# x-Link.net
KiCad netlist of a schematic drawn in Altium Designer
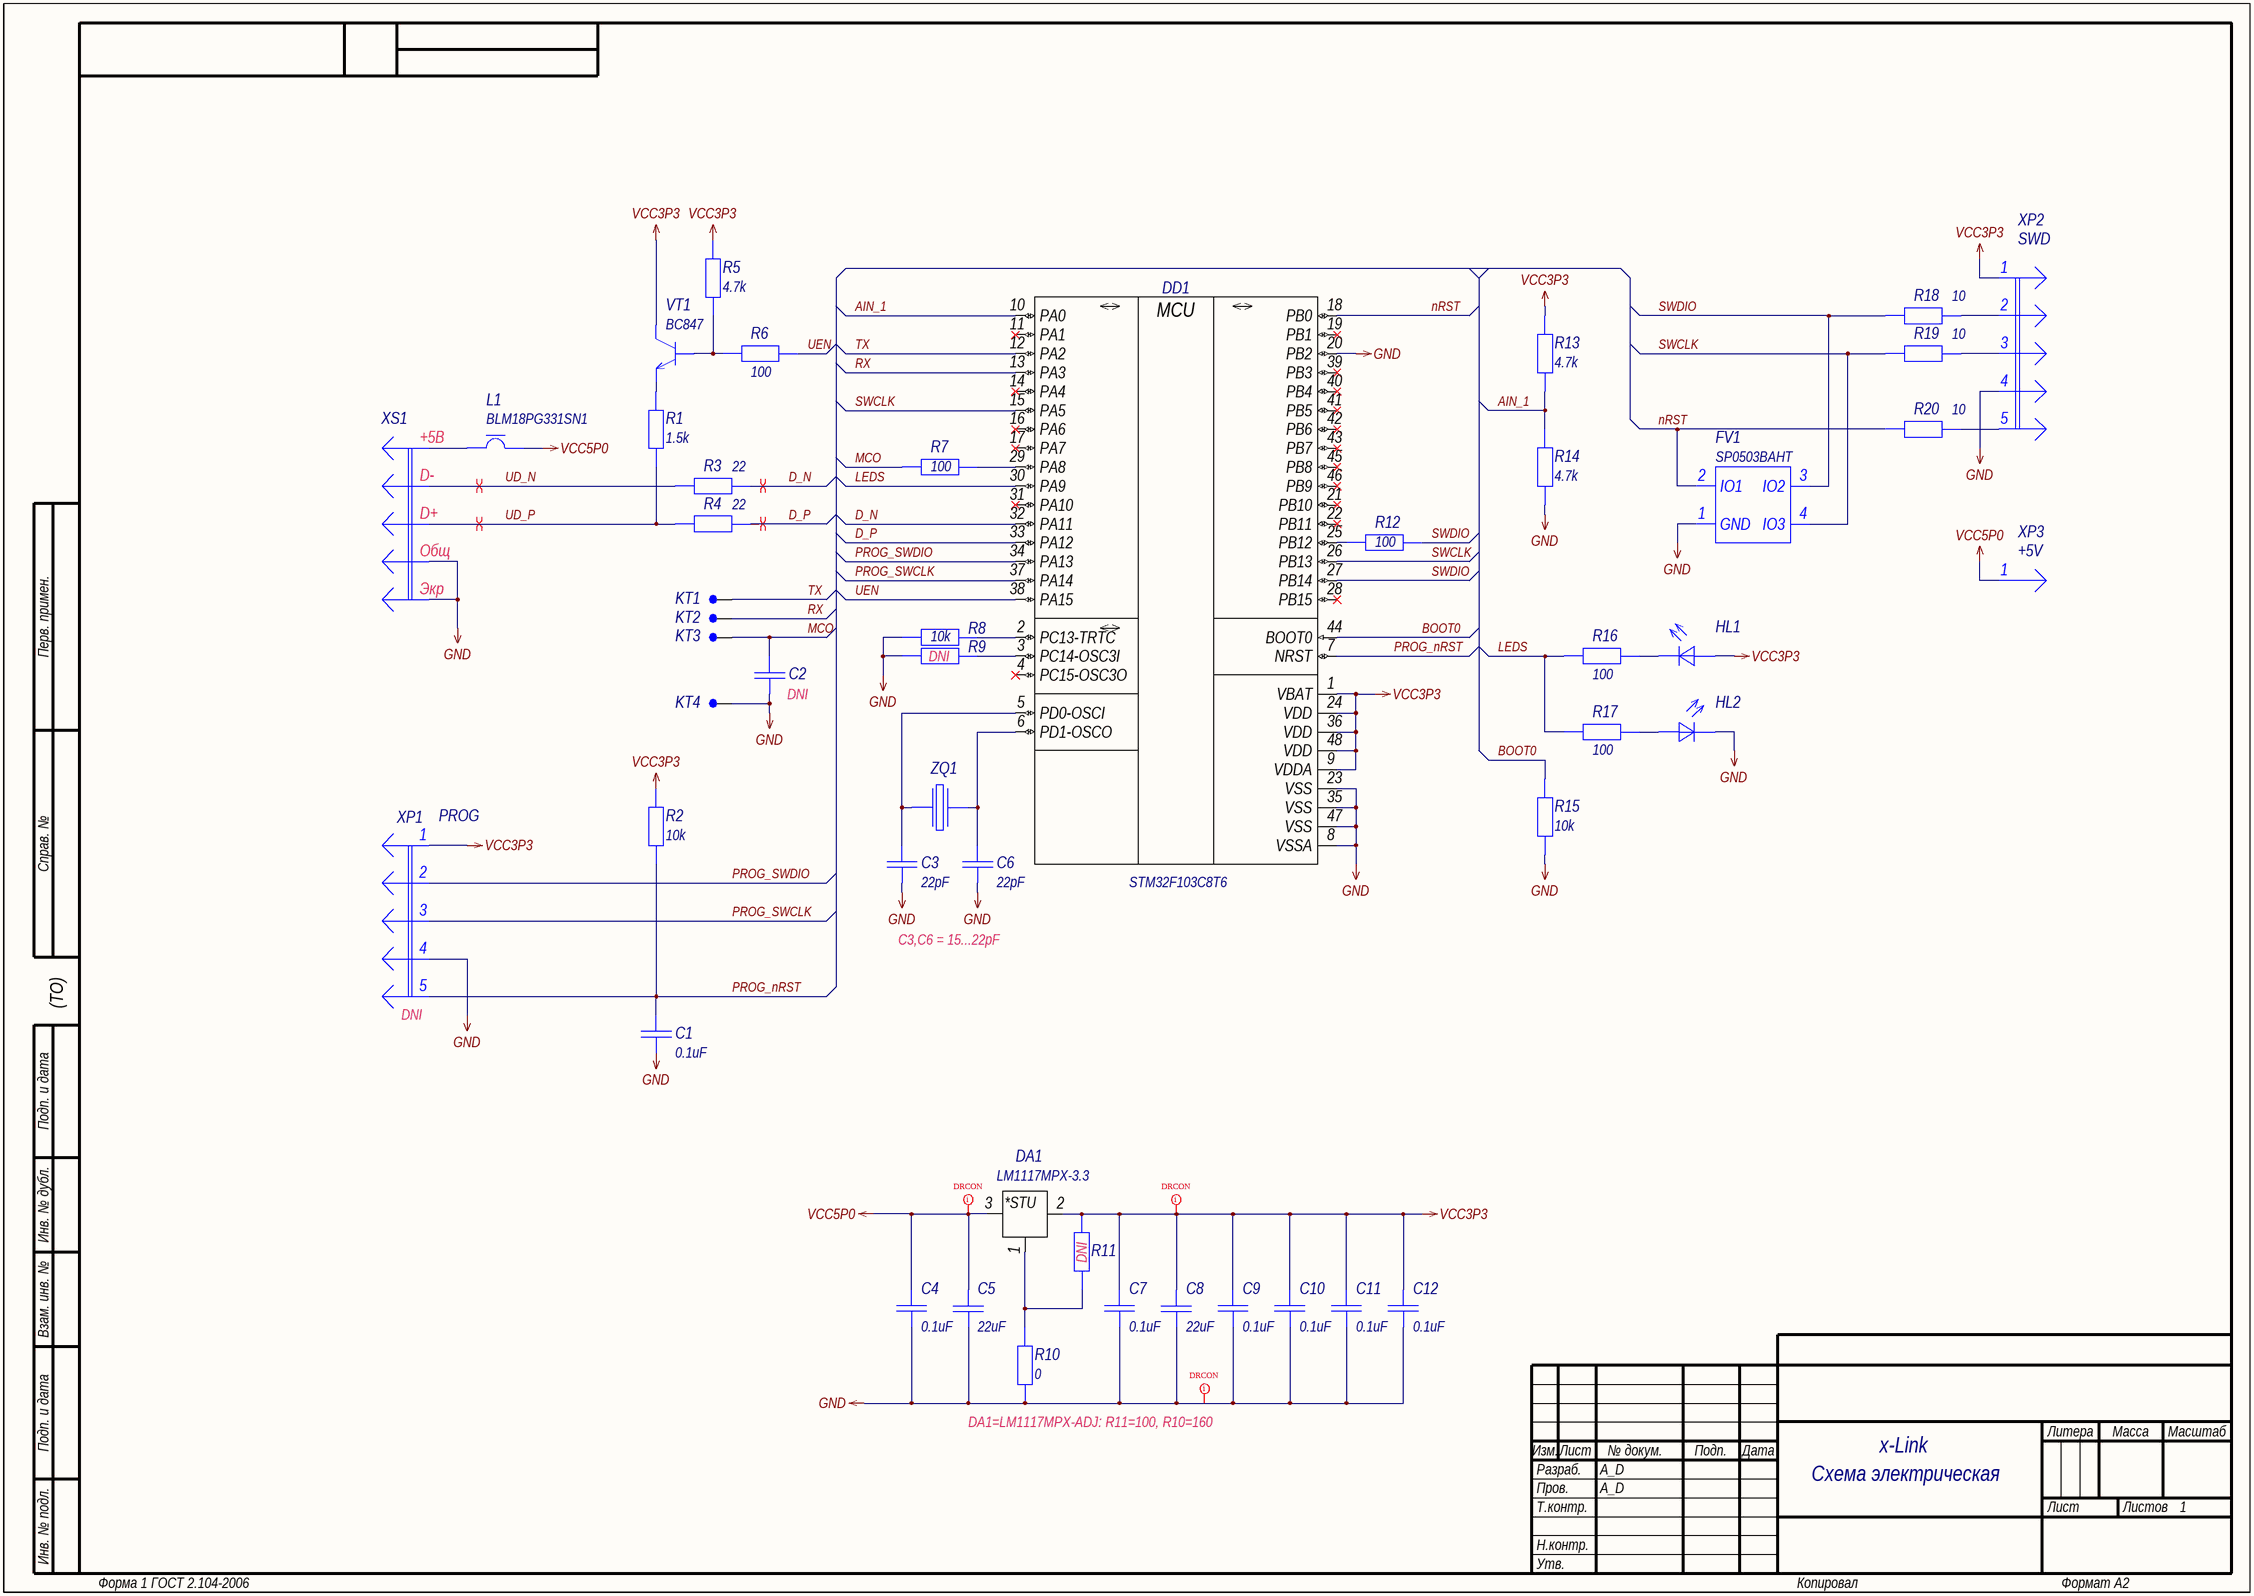
[diagram p0: x-Link.SchDoc]

(export (version "E")
  (design (tool "Eeschema 10.0.6"))
  (components
    (comp (ref "C1")
      (value "0.1uF")
      (footprint "C0603_L")
      (fields
        (field (name "PART NUMBER") "GRM188R71C104KA01D")
        (field (name "VOLTAGE") "16V")
        (field (name "TOLERANCE") "±10%")
        (field (name "PUBLISHER") "Andrew Danich")
      )
      (libsource (lib "Lib_IMP_GOST") (part "Capacitor"))
    )
    (comp (ref "C2")
      (value "Capacitor")
      (footprint "C0603_L")
      (fields
        (field (name "PART NUMBER") "GRM1885C1H220JA01D")
        (field (name "VOLTAGE") "50V")
        (field (name "TOLERANCE") "±5%")
        (field (name "PUBLISHER") "Andrew Danich")
      )
      (libsource (lib "Lib_IMP_GOST") (part "Capacitor"))
    )
    (comp (ref "C3")
      (value "22pF")
      (footprint "C0603_L")
      (fields
        (field (name "PART NUMBER") "GRM1885C1H220JA01D")
        (field (name "VOLTAGE") "50V")
        (field (name "TOLERANCE") "±5%")
        (field (name "PUBLISHER") "Andrew Danich")
      )
      (libsource (lib "Lib_IMP_GOST") (part "Capacitor"))
    )
    (comp (ref "C4")
      (value "0.1uF")
      (footprint "C0603_L")
      (fields
        (field (name "PART NUMBER") "GRM188R71C104KA01D")
        (field (name "VOLTAGE") "16V")
        (field (name "TOLERANCE") "±10%")
        (field (name "PUBLISHER") "Andrew Danich")
      )
      (libsource (lib "Lib_IMP_GOST") (part "Capacitor"))
    )
    (comp (ref "C5")
      (value "22uF")
      (footprint "C0805_L")
      (fields
        (field (name "PART NUMBER") "GRM21BR60J226ME39L")
        (field (name "VOLTAGE") "6.3V")
        (field (name "TOLERANCE") "±20%")
        (field (name "PUBLISHER") "Andrew Danich")
      )
      (libsource (lib "Lib_IMP_GOST") (part "Capacitor"))
    )
    (comp (ref "C6")
      (value "22pF")
      (footprint "C0603_L")
      (fields
        (field (name "PART NUMBER") "GRM1885C1H220JA01D")
        (field (name "VOLTAGE") "50V")
        (field (name "TOLERANCE") "±5%")
        (field (name "PUBLISHER") "Andrew Danich")
      )
      (libsource (lib "Lib_IMP_GOST") (part "Capacitor"))
    )
    (comp (ref "C7")
      (value "0.1uF")
      (footprint "C0603_L")
      (fields
        (field (name "PART NUMBER") "GRM188R71C104KA01D")
        (field (name "VOLTAGE") "16V")
        (field (name "TOLERANCE") "±10%")
        (field (name "PUBLISHER") "Andrew Danich")
      )
      (libsource (lib "Lib_IMP_GOST") (part "Capacitor"))
    )
    (comp (ref "C8")
      (value "22uF")
      (footprint "C0805_L")
      (fields
        (field (name "PART NUMBER") "GRM21BR60J226ME39L")
        (field (name "VOLTAGE") "6.3V")
        (field (name "TOLERANCE") "±20%")
        (field (name "PUBLISHER") "Andrew Danich")
      )
      (libsource (lib "Lib_IMP_GOST") (part "Capacitor"))
    )
    (comp (ref "C9")
      (value "0.1uF")
      (footprint "C0603_L")
      (fields
        (field (name "PART NUMBER") "GRM188R71C104KA01D")
        (field (name "VOLTAGE") "16V")
        (field (name "TOLERANCE") "±10%")
        (field (name "PUBLISHER") "Andrew Danich")
      )
      (libsource (lib "Lib_IMP_GOST") (part "Capacitor"))
    )
    (comp (ref "C10")
      (value "0.1uF")
      (footprint "C0603_L")
      (fields
        (field (name "PART NUMBER") "GRM188R71C104KA01D")
        (field (name "VOLTAGE") "16V")
        (field (name "TOLERANCE") "±10%")
        (field (name "PUBLISHER") "Andrew Danich")
      )
      (libsource (lib "Lib_IMP_GOST") (part "Capacitor"))
    )
    (comp (ref "C11")
      (value "0.1uF")
      (footprint "C0603_L")
      (fields
        (field (name "PART NUMBER") "GRM188R71C104KA01D")
        (field (name "VOLTAGE") "16V")
        (field (name "TOLERANCE") "±10%")
        (field (name "PUBLISHER") "Andrew Danich")
      )
      (libsource (lib "Lib_IMP_GOST") (part "Capacitor"))
    )
    (comp (ref "C12")
      (value "0.1uF")
      (footprint "C0603_L")
      (fields
        (field (name "PART NUMBER") "GRM188R71C104KA01D")
        (field (name "VOLTAGE") "16V")
        (field (name "TOLERANCE") "±10%")
        (field (name "PUBLISHER") "Andrew Danich")
      )
      (libsource (lib "Lib_IMP_GOST") (part "Capacitor"))
    )
    (comp (ref "DA1")
      (value "LM1117MPX-3.3")
      (footprint "SOT-223")
      (fields (field (name "Comment") "LM1117-Series") (field (name "PUBLISHER") "Andrew Danich"))
      (libsource (lib "Lib_IMP_GOST") (part "LM1117-Series"))
    )
    (comp (ref "DD1")
      (value "STM32F103C8T6")
      (footprint "LQFP-48")
      (fields
        (field (name "MANUFACTURER") "STMicroelectronics")
        (field (name "Comment") "STM32F103Cxxx-Series")
        (field (name "PUBLISHER") "Andrew Danich")
      )
      (libsource (lib "Lib_IMP_GOST") (part "STM32F103Cxxx-Series"))
    )
    (comp (ref "FV1")
      (value "SP0503BAHT")
      (footprint "SOT-143")
      (fields (field (name "MANUFACTURER") "LittleFuse") (field (name "PUBLISHER") "Andrew Danich"))
      (libsource (lib "Lib_IMP_GOST") (part "SP0503BAHT"))
    )
    (comp (ref "HL1")
      (value "Text")
      (footprint "LD0603_L")
      (fields (field (name "PART NUMBER") "BL-LS0603GC") (field (name "PUBLISHER") "Andrew Danich"))
      (libsource (lib "Lib_IMP_GOST") (part "Led-1"))
    )
    (comp (ref "HL2")
      (value "Text")
      (footprint "LD0603_L")
      (fields (field (name "PART NUMBER") "BL-LS0603HC") (field (name "PUBLISHER") "Andrew Danich"))
      (libsource (lib "Lib_IMP_GOST") (part "Led-1"))
    )
    (comp (ref "KT1")
      (value "TX")
      (footprint "TP-SMT-C-1mm-1")
      (fields (field (name "PART NUMBER") "КТ-SMT-1") (field (name "PUBLISHER") "Andrew Danich"))
      (libsource (lib "Lib_IMP_GOST") (part "TP-S-1"))
    )
    (comp (ref "KT2")
      (value "RX")
      (footprint "TP-SMT-C-1mm-1")
      (fields (field (name "PART NUMBER") "КТ-SMT-1") (field (name "PUBLISHER") "Andrew Danich"))
      (libsource (lib "Lib_IMP_GOST") (part "TP-S-1"))
    )
    (comp (ref "KT3")
      (value "MCO")
      (footprint "TP-SMT-C-1mm-1")
      (fields (field (name "PART NUMBER") "КТ-SMT-1") (field (name "PUBLISHER") "Andrew Danich"))
      (libsource (lib "Lib_IMP_GOST") (part "TP-S-1"))
    )
    (comp (ref "KT4")
      (value "GND")
      (footprint "TP-SMT-C-1mm-1")
      (fields (field (name "PART NUMBER") "КТ-SMT-1") (field (name "PUBLISHER") "Andrew Danich"))
      (libsource (lib "Lib_IMP_GOST") (part "TP-S-1"))
    )
    (comp (ref "L1")
      (value "BLM18PG331SN1")
      (footprint "L0603_L")
      (fields
        (field (name "MANUFACTURER") "Murata")
        (field (name "Comment") "FerriteBead")
        (field (name "PUBLISHER") "Andrew Danich")
      )
      (libsource (lib "Lib_IMP_GOST") (part "FerriteBead"))
    )
    (comp (ref "R1")
      (value "1.5k")
      (footprint "R0603_L")
      (fields
        (field (name "PART NUMBER") "RC0603JR-071K5L")
        (field (name "TOLERANCE") "±5%")
        (field (name "MANUFACTURER") "Yageo")
        (field (name "PUBLISHER") "Andrew Danich")
      )
      (libsource (lib "Lib_IMP_GOST") (part "Resistor"))
    )
    (comp (ref "R2")
      (value "10k")
      (footprint "R0603_L")
      (fields
        (field (name "PART NUMBER") "RC0603JR-0710KL")
        (field (name "TOLERANCE") "±5%")
        (field (name "MANUFACTURER") "Yageo")
        (field (name "PUBLISHER") "Andrew Danich")
      )
      (libsource (lib "Lib_IMP_GOST") (part "Resistor"))
    )
    (comp (ref "R3")
      (value "22")
      (footprint "R0603_L")
      (fields
        (field (name "PART NUMBER") "RC0603JR-0722RL")
        (field (name "TOLERANCE") "±5%")
        (field (name "MANUFACTURER") "Yageo")
        (field (name "PUBLISHER") "Andrew Danich")
      )
      (libsource (lib "Lib_IMP_GOST") (part "Resistor"))
    )
    (comp (ref "R4")
      (value "22")
      (footprint "R0603_L")
      (fields
        (field (name "PART NUMBER") "RC0603JR-0722RL")
        (field (name "TOLERANCE") "±5%")
        (field (name "MANUFACTURER") "Yageo")
        (field (name "PUBLISHER") "Andrew Danich")
      )
      (libsource (lib "Lib_IMP_GOST") (part "Resistor"))
    )
    (comp (ref "R5")
      (value "4.7k")
      (footprint "R0603_L")
      (fields
        (field (name "PART NUMBER") "RC0603JR-074K7L")
        (field (name "TOLERANCE") "±5%")
        (field (name "MANUFACTURER") "Yageo")
        (field (name "PUBLISHER") "Andrew Danich")
      )
      (libsource (lib "Lib_IMP_GOST") (part "Resistor"))
    )
    (comp (ref "R6")
      (value "100")
      (footprint "R0603_L")
      (fields
        (field (name "PART NUMBER") "RC0603JR-07100R")
        (field (name "TOLERANCE") "±5%")
        (field (name "MANUFACTURER") "Yageo")
        (field (name "PUBLISHER") "Andrew Danich")
      )
      (libsource (lib "Lib_IMP_GOST") (part "Resistor"))
    )
    (comp (ref "R7")
      (value "100")
      (footprint "R0603_L")
      (fields
        (field (name "PART NUMBER") "RC0603JR-07100R")
        (field (name "TOLERANCE") "±5%")
        (field (name "MANUFACTURER") "Yageo")
        (field (name "PUBLISHER") "Andrew Danich")
      )
      (libsource (lib "Lib_IMP_GOST") (part "Resistor"))
    )
    (comp (ref "R8")
      (value "10k")
      (footprint "R0603_L")
      (fields
        (field (name "PART NUMBER") "RC0603JR-0710KL")
        (field (name "TOLERANCE") "±5%")
        (field (name "MANUFACTURER") "Yageo")
        (field (name "PUBLISHER") "Andrew Danich")
      )
      (libsource (lib "Lib_IMP_GOST") (part "Resistor"))
    )
    (comp (ref "R9")
      (value "Resistor")
      (footprint "R0603_L")
      (fields
        (field (name "PART NUMBER") "RC0603JR-0710KL")
        (field (name "TOLERANCE") "±5%")
        (field (name "MANUFACTURER") "Yageo")
        (field (name "PUBLISHER") "Andrew Danich")
      )
      (libsource (lib "Lib_IMP_GOST") (part "Resistor"))
    )
    (comp (ref "R10")
      (value "0")
      (footprint "R0603_L")
      (fields
        (field (name "PART NUMBER") "RC0603JR-070R")
        (field (name "TOLERANCE") "±5%")
        (field (name "MANUFACTURER") "Yageo")
        (field (name "PUBLISHER") "Andrew Danich")
      )
      (libsource (lib "Lib_IMP_GOST") (part "Resistor"))
    )
    (comp (ref "R11")
      (value "Resistor")
      (footprint "R0603_L")
      (fields
        (field (name "PART NUMBER") "RC0603JR-070R")
        (field (name "TOLERANCE") "±5%")
        (field (name "MANUFACTURER") "Yageo")
        (field (name "PUBLISHER") "Andrew Danich")
      )
      (libsource (lib "Lib_IMP_GOST") (part "Resistor"))
    )
    (comp (ref "R12")
      (value "100")
      (footprint "R0603_L")
      (fields
        (field (name "PART NUMBER") "RC0603JR-07100R")
        (field (name "TOLERANCE") "±5%")
        (field (name "MANUFACTURER") "Yageo")
        (field (name "PUBLISHER") "Andrew Danich")
      )
      (libsource (lib "Lib_IMP_GOST") (part "Resistor"))
    )
    (comp (ref "R13")
      (value "4.7k")
      (footprint "R0603_L")
      (fields
        (field (name "PART NUMBER") "RC0603JR-074K7L")
        (field (name "TOLERANCE") "±5%")
        (field (name "MANUFACTURER") "Yageo")
        (field (name "PUBLISHER") "Andrew Danich")
      )
      (libsource (lib "Lib_IMP_GOST") (part "Resistor"))
    )
    (comp (ref "R14")
      (value "4.7k")
      (footprint "R0603_L")
      (fields
        (field (name "PART NUMBER") "RC0603JR-074K7L")
        (field (name "TOLERANCE") "±5%")
        (field (name "MANUFACTURER") "Yageo")
        (field (name "PUBLISHER") "Andrew Danich")
      )
      (libsource (lib "Lib_IMP_GOST") (part "Resistor"))
    )
    (comp (ref "R15")
      (value "10k")
      (footprint "R0603_L")
      (fields
        (field (name "PART NUMBER") "RC0603JR-0710KL")
        (field (name "TOLERANCE") "±5%")
        (field (name "MANUFACTURER") "Yageo")
        (field (name "PUBLISHER") "Andrew Danich")
      )
      (libsource (lib "Lib_IMP_GOST") (part "Resistor"))
    )
    (comp (ref "R16")
      (value "100")
      (footprint "R0603_L")
      (fields
        (field (name "PART NUMBER") "RC0603JR-07100R")
        (field (name "TOLERANCE") "±5%")
        (field (name "MANUFACTURER") "Yageo")
        (field (name "PUBLISHER") "Andrew Danich")
      )
      (libsource (lib "Lib_IMP_GOST") (part "Resistor"))
    )
    (comp (ref "R17")
      (value "100")
      (footprint "R0603_L")
      (fields
        (field (name "PART NUMBER") "RC0603JR-07100R")
        (field (name "TOLERANCE") "±5%")
        (field (name "MANUFACTURER") "Yageo")
        (field (name "PUBLISHER") "Andrew Danich")
      )
      (libsource (lib "Lib_IMP_GOST") (part "Resistor"))
    )
    (comp (ref "R18")
      (value "10")
      (footprint "R0603_L")
      (fields
        (field (name "PART NUMBER") "RC0603JR-0710RL")
        (field (name "TOLERANCE") "±5%")
        (field (name "MANUFACTURER") "Yageo")
        (field (name "PUBLISHER") "Andrew Danich")
      )
      (libsource (lib "Lib_IMP_GOST") (part "Resistor"))
    )
    (comp (ref "R19")
      (value "10")
      (footprint "R0603_L")
      (fields
        (field (name "PART NUMBER") "RC0603JR-0710RL")
        (field (name "TOLERANCE") "±5%")
        (field (name "MANUFACTURER") "Yageo")
        (field (name "PUBLISHER") "Andrew Danich")
      )
      (libsource (lib "Lib_IMP_GOST") (part "Resistor"))
    )
    (comp (ref "R20")
      (value "10")
      (footprint "R0603_L")
      (fields
        (field (name "PART NUMBER") "RC0603JR-0710RL")
        (field (name "TOLERANCE") "±5%")
        (field (name "MANUFACTURER") "Yageo")
        (field (name "PUBLISHER") "Andrew Danich")
      )
      (libsource (lib "Lib_IMP_GOST") (part "Resistor"))
    )
    (comp (ref "VT1")
      (value "BC847")
      (footprint "SOT-23")
      (fields (field (name "Comment") "BJT-NPN") (field (name "PUBLISHER") "Andrew Danich"))
      (libsource (lib "Lib_IMP_GOST") (part "BJT-NPN"))
    )
    (comp (ref "XP1")
      (value "PROG")
      (footprint "PLS-5")
      (fields (field (name "PART NUMBER") "PLS-5") (field (name "PUBLISHER") "Andrew Danich"))
      (libsource (lib "Lib_IMP_GOST") (part "Con-5-M"))
    )
    (comp (ref "XP2")
      (value "SWD")
      (footprint "PLS-5")
      (fields (field (name "PART NUMBER") "PLS-5") (field (name "PUBLISHER") "Andrew Danich"))
      (libsource (lib "Lib_IMP_GOST") (part "Con-5-M"))
    )
    (comp (ref "XP3")
      (value "+5V")
      (footprint "PLS-1")
      (fields (field (name "PART NUMBER") "PLS-1") (field (name "PUBLISHER") "Andrew Danich"))
      (libsource (lib "Lib_IMP_GOST") (part "Con-1-M"))
    )
    (comp (ref "XS1")
      (value "Text")
      (footprint "DS1097")
      (fields
        (field (name "PART NUMBER") "DS1097-B")
        (field (name "MANUFACTURER") "Connfly Electronic Co., Ltd")
        (field (name "PUBLISHER") "Andrew Danich")
      )
      (libsource (lib "Lib_IMP_GOST") (part "Con-5-M-USB"))
    )
    (comp (ref "ZQ1")
      (value "Crystal")
      (footprint "SMD 5x3.2mm")
      (fields
        (field (name "PART NUMBER") "KX-9A 8.0 MHz 30/50/100 16 pF")
        (field (name "MANUFACTURER") "Geyer")
        (field (name "PUBLISHER") "Andrew Danich")
      )
      (libsource (lib "Lib_IMP_GOST") (part "Crystal"))
    )
  )
  (nets
    (net (code "1") (name "/AIN_1") (class "Default")
      (node (ref "DD1") (pin "10") (pinfunction "PA0_10") (pintype "bidirectional"))
      (node (ref "R13") (pin "1") (pinfunction "1_1") (pintype "passive"))
      (node (ref "R14") (pin "2") (pinfunction "2_2") (pintype "passive"))
    )
    (net (code "2") (name "/BOOT0") (class "Default")
      (node (ref "DD1") (pin "44") (pinfunction "BOOT0_44") (pintype "input"))
      (node (ref "R15") (pin "2") (pinfunction "2_2") (pintype "passive"))
    )
    (net (code "3") (name "/D_N") (class "Default")
      (node (ref "DD1") (pin "32") (pinfunction "PA11_32") (pintype "bidirectional"))
      (node (ref "R3") (pin "2") (pinfunction "2_2") (pintype "passive"))
    )
    (net (code "4") (name "/D_P") (class "Default")
      (node (ref "DD1") (pin "33") (pinfunction "PA12_33") (pintype "bidirectional"))
      (node (ref "R4") (pin "2") (pinfunction "2_2") (pintype "passive"))
    )
    (net (code "5") (name "/LEDS") (class "Default")
      (node (ref "DD1") (pin "30") (pinfunction "PA9_30") (pintype "bidirectional"))
      (node (ref "R16") (pin "2") (pinfunction "2_2") (pintype "passive"))
      (node (ref "R17") (pin "2") (pinfunction "2_2") (pintype "passive"))
    )
    (net (code "6") (name "/MCO") (class "Default")
      (node (ref "C2") (pin "2") (pinfunction "2_2") (pintype "passive"))
      (node (ref "KT3") (pin "1") (pinfunction "1_1") (pintype "passive"))
      (node (ref "R7") (pin "2") (pinfunction "2_2") (pintype "passive"))
    )
    (net (code "7") (name "/PROG_SWCLK") (class "Default")
      (node (ref "DD1") (pin "37") (pinfunction "PA14_37") (pintype "bidirectional"))
      (node (ref "XP1") (pin "3") (pintype "passive"))
    )
    (net (code "8") (name "/PROG_SWDIO") (class "Default")
      (node (ref "DD1") (pin "34") (pinfunction "PA13_34") (pintype "bidirectional"))
      (node (ref "XP1") (pin "2") (pintype "passive"))
    )
    (net (code "9") (name "/PROG_nRST") (class "Default")
      (node (ref "C1") (pin "2") (pinfunction "2_2") (pintype "passive"))
      (node (ref "DD1") (pin "7") (pinfunction "NRST_7") (pintype "bidirectional"))
      (node (ref "R2") (pin "2") (pinfunction "2_2") (pintype "passive"))
      (node (ref "XP1") (pin "5") (pintype "passive"))
    )
    (net (code "10") (name "/RX") (class "Default")
      (node (ref "DD1") (pin "13") (pinfunction "PA3_13") (pintype "bidirectional"))
      (node (ref "KT2") (pin "1") (pinfunction "1_1") (pintype "passive"))
    )
    (net (code "11") (name "/SWCLK") (class "Default")
      (node (ref "DD1") (pin "15") (pinfunction "PA5_15") (pintype "bidirectional"))
      (node (ref "DD1") (pin "26") (pinfunction "PB13_26") (pintype "bidirectional"))
      (node (ref "FV1") (pin "4") (pinfunction "IO3_4") (pintype "passive"))
      (node (ref "R19") (pin "1") (pinfunction "1_1") (pintype "passive"))
    )
    (net (code "12") (name "/SWDIO") (class "Default")
      (node (ref "DD1") (pin "27") (pinfunction "PB14_27") (pintype "bidirectional"))
      (node (ref "FV1") (pin "3") (pinfunction "IO2_3") (pintype "passive"))
      (node (ref "R12") (pin "2") (pinfunction "2_2") (pintype "passive"))
      (node (ref "R18") (pin "1") (pinfunction "1_1") (pintype "passive"))
    )
    (net (code "13") (name "/TX") (class "Default")
      (node (ref "DD1") (pin "12") (pinfunction "PA2_12") (pintype "bidirectional"))
      (node (ref "KT1") (pin "1") (pinfunction "1_1") (pintype "passive"))
    )
    (net (code "14") (name "/UD_N") (class "Default")
      (node (ref "R3") (pin "1") (pinfunction "1_1") (pintype "passive"))
      (node (ref "XS1") (pin "2") (pintype "passive"))
    )
    (net (code "15") (name "/UD_P") (class "Default")
      (node (ref "R1") (pin "1") (pinfunction "1_1") (pintype "passive"))
      (node (ref "R4") (pin "1") (pinfunction "1_1") (pintype "passive"))
      (node (ref "XS1") (pin "3") (pintype "passive"))
    )
    (net (code "16") (name "/UEN") (class "Default")
      (node (ref "DD1") (pin "38") (pinfunction "PA15_38") (pintype "bidirectional"))
      (node (ref "R6") (pin "1") (pinfunction "1_1") (pintype "passive"))
    )
    (net (code "17") (name "/nRST") (class "Default")
      (node (ref "DD1") (pin "18") (pinfunction "PB0_18") (pintype "bidirectional"))
      (node (ref "FV1") (pin "2") (pinfunction "IO1_2") (pintype "passive"))
      (node (ref "R20") (pin "1") (pinfunction "1_1") (pintype "passive"))
    )
    (net (code "18") (name "GND") (class "Default")
      (node (ref "C1") (pin "1") (pinfunction "1_1") (pintype "passive"))
      (node (ref "C10") (pin "1") (pinfunction "1_1") (pintype "passive"))
      (node (ref "C11") (pin "1") (pinfunction "1_1") (pintype "passive"))
      (node (ref "C12") (pin "1") (pinfunction "1_1") (pintype "passive"))
      (node (ref "C2") (pin "1") (pinfunction "1_1") (pintype "passive"))
      (node (ref "C3") (pin "1") (pinfunction "1_1") (pintype "passive"))
      (node (ref "C4") (pin "1") (pinfunction "1_1") (pintype "passive"))
      (node (ref "C5") (pin "2") (pinfunction "2_2") (pintype "passive"))
      (node (ref "C6") (pin "1") (pinfunction "1_1") (pintype "passive"))
      (node (ref "C7") (pin "1") (pinfunction "1_1") (pintype "passive"))
      (node (ref "C8") (pin "2") (pinfunction "2_2") (pintype "passive"))
      (node (ref "C9") (pin "1") (pinfunction "1_1") (pintype "passive"))
      (node (ref "DD1") (pin "20") (pinfunction "PB2_20") (pintype "bidirectional"))
      (node (ref "DD1") (pin "23") (pinfunction "VSS_23") (pintype "power_in"))
      (node (ref "DD1") (pin "35") (pinfunction "VSS_35") (pintype "power_in"))
      (node (ref "DD1") (pin "47") (pinfunction "VSS_47") (pintype "power_in"))
      (node (ref "DD1") (pin "8") (pinfunction "VSSA_8") (pintype "power_in"))
      (node (ref "FV1") (pin "1") (pinfunction "GND_1") (pintype "power_in"))
      (node (ref "HL2") (pin "2") (pinfunction "К_2") (pintype "passive"))
      (node (ref "KT4") (pin "1") (pinfunction "1_1") (pintype "passive"))
      (node (ref "R10") (pin "1") (pinfunction "1_1") (pintype "passive"))
      (node (ref "R14") (pin "1") (pinfunction "1_1") (pintype "passive"))
      (node (ref "R15") (pin "1") (pinfunction "1_1") (pintype "passive"))
      (node (ref "R8") (pin "1") (pinfunction "1_1") (pintype "passive"))
      (node (ref "R9") (pin "1") (pinfunction "1_1") (pintype "passive"))
      (node (ref "XP1") (pin "4") (pintype "passive"))
      (node (ref "XP2") (pin "4") (pintype "passive"))
      (node (ref "XS1") (pin "4") (pintype "passive"))
      (node (ref "XS1") (pin "5") (pintype "passive"))
    )
    (net (code "19") (name "Net-(DA1-Adj{slash}GND)") (class "Default")
      (node (ref "DA1") (pin "1") (pinfunction "Adj/GND_1") (pintype "passive"))
      (node (ref "R10") (pin "2") (pinfunction "2_2") (pintype "passive"))
      (node (ref "R11") (pin "1") (pinfunction "1_1") (pintype "passive"))
    )
    (net (code "20") (name "Net-(DD1-PA8)") (class "Default")
      (node (ref "DD1") (pin "29") (pinfunction "PA8_29") (pintype "bidirectional"))
      (node (ref "R7") (pin "1") (pinfunction "1_1") (pintype "passive"))
    )
    (net (code "21") (name "Net-(DD1-PB12)") (class "Default")
      (node (ref "DD1") (pin "25") (pinfunction "PB12_25") (pintype "bidirectional"))
      (node (ref "R12") (pin "1") (pinfunction "1_1") (pintype "passive"))
    )
    (net (code "22") (name "Net-(DD1-PC13-TRTC)") (class "Default")
      (node (ref "DD1") (pin "2") (pinfunction "PC13-TRTC_2") (pintype "bidirectional"))
      (node (ref "R8") (pin "2") (pinfunction "2_2") (pintype "passive"))
    )
    (net (code "23") (name "Net-(DD1-PC14-OSC3I)") (class "Default")
      (node (ref "DD1") (pin "3") (pinfunction "PC14-OSC3I_3") (pintype "bidirectional"))
      (node (ref "R9") (pin "2") (pinfunction "2_2") (pintype "passive"))
    )
    (net (code "24") (name "Net-(DD1-PD0-OSCI)") (class "Default")
      (node (ref "C3") (pin "2") (pinfunction "2_2") (pintype "passive"))
      (node (ref "DD1") (pin "5") (pinfunction "PD0-OSCI_5") (pintype "bidirectional"))
      (node (ref "ZQ1") (pin "1") (pinfunction "1_1") (pintype "passive"))
    )
    (net (code "25") (name "Net-(DD1-PD1-OSCO)") (class "Default")
      (node (ref "C6") (pin "2") (pinfunction "2_2") (pintype "passive"))
      (node (ref "DD1") (pin "6") (pinfunction "PD1-OSCO_6") (pintype "bidirectional"))
      (node (ref "ZQ1") (pin "3") (pinfunction "3_3") (pintype "passive"))
    )
    (net (code "26") (name "Net-(HL1-К)") (class "Default")
      (node (ref "HL1") (pin "2") (pinfunction "К_2") (pintype "passive"))
      (node (ref "R16") (pin "1") (pinfunction "1_1") (pintype "passive"))
    )
    (net (code "27") (name "Net-(HL2-А)") (class "Default")
      (node (ref "HL2") (pin "1") (pinfunction "А_1") (pintype "passive"))
      (node (ref "R17") (pin "1") (pinfunction "1_1") (pintype "passive"))
    )
    (net (code "28") (name "Net-(L1-Pad1)") (class "Default")
      (node (ref "L1") (pin "1") (pinfunction "1_1") (pintype "passive"))
      (node (ref "XS1") (pin "1") (pintype "passive"))
    )
    (net (code "29") (name "Net-(R18-Pad2)") (class "Default")
      (node (ref "R18") (pin "2") (pinfunction "2_2") (pintype "passive"))
      (node (ref "XP2") (pin "2") (pintype "passive"))
    )
    (net (code "30") (name "Net-(R19-Pad2)") (class "Default")
      (node (ref "R19") (pin "2") (pinfunction "2_2") (pintype "passive"))
      (node (ref "XP2") (pin "3") (pintype "passive"))
    )
    (net (code "31") (name "Net-(R20-Pad2)") (class "Default")
      (node (ref "R20") (pin "2") (pinfunction "2_2") (pintype "passive"))
      (node (ref "XP2") (pin "5") (pintype "passive"))
    )
    (net (code "32") (name "Net-(VT1-Б)") (class "Default")
      (node (ref "R5") (pin "1") (pinfunction "1_1") (pintype "passive"))
      (node (ref "R6") (pin "2") (pinfunction "2_2") (pintype "passive"))
      (node (ref "VT1") (pin "1") (pinfunction "Б_1") (pintype "passive"))
    )
    (net (code "33") (name "Net-(VT1-Э)") (class "Default")
      (node (ref "R1") (pin "2") (pinfunction "2_2") (pintype "passive"))
      (node (ref "VT1") (pin "3") (pinfunction "Э_3") (pintype "passive"))
    )
    (net (code "34") (name "VCC3P3") (class "Default")
      (node (ref "C10") (pin "2") (pinfunction "2_2") (pintype "passive"))
      (node (ref "C11") (pin "2") (pinfunction "2_2") (pintype "passive"))
      (node (ref "C12") (pin "2") (pinfunction "2_2") (pintype "passive"))
      (node (ref "C7") (pin "2") (pinfunction "2_2") (pintype "passive"))
      (node (ref "C8") (pin "1") (pinfunction "1_1") (pintype "passive"))
      (node (ref "C9") (pin "2") (pinfunction "2_2") (pintype "passive"))
      (node (ref "DA1") (pin "2") (pinfunction "Out_2") (pintype "passive"))
      (node (ref "DD1") (pin "1") (pinfunction "VBAT_1") (pintype "power_in"))
      (node (ref "DD1") (pin "24") (pinfunction "VDD_24") (pintype "power_in"))
      (node (ref "DD1") (pin "36") (pinfunction "VDD_36") (pintype "power_in"))
      (node (ref "DD1") (pin "48") (pinfunction "VDD_48") (pintype "power_in"))
      (node (ref "DD1") (pin "9") (pinfunction "VDDA_9") (pintype "power_in"))
      (node (ref "HL1") (pin "1") (pinfunction "А_1") (pintype "passive"))
      (node (ref "R11") (pin "2") (pinfunction "2_2") (pintype "passive"))
      (node (ref "R13") (pin "2") (pinfunction "2_2") (pintype "passive"))
      (node (ref "R2") (pin "1") (pinfunction "1_1") (pintype "passive"))
      (node (ref "R5") (pin "2") (pinfunction "2_2") (pintype "passive"))
      (node (ref "VT1") (pin "2") (pinfunction "К_2") (pintype "passive"))
      (node (ref "XP1") (pin "1") (pintype "passive"))
      (node (ref "XP2") (pin "1") (pintype "passive"))
    )
    (net (code "35") (name "VCC5P0") (class "Default")
      (node (ref "C4") (pin "2") (pinfunction "2_2") (pintype "passive"))
      (node (ref "C5") (pin "1") (pinfunction "1_1") (pintype "passive"))
      (node (ref "DA1") (pin "3") (pinfunction "In_3") (pintype "passive"))
      (node (ref "L1") (pin "2") (pinfunction "2_2") (pintype "passive"))
      (node (ref "XP3") (pin "1") (pintype "passive"))
    )
    (net (code "36") (name "unconnected-(DD1-PA1-Pad11)") (class "Default")
      (node (ref "DD1") (pin "11") (pinfunction "PA1_11") (pintype "bidirectional+no_connect"))
    )
    (net (code "37") (name "unconnected-(DD1-PA4-Pad14)") (class "Default")
      (node (ref "DD1") (pin "14") (pinfunction "PA4_14") (pintype "bidirectional+no_connect"))
    )
    (net (code "38") (name "unconnected-(DD1-PA6-Pad16)") (class "Default")
      (node (ref "DD1") (pin "16") (pinfunction "PA6_16") (pintype "bidirectional+no_connect"))
    )
    (net (code "39") (name "unconnected-(DD1-PA7-Pad17)") (class "Default")
      (node (ref "DD1") (pin "17") (pinfunction "PA7_17") (pintype "bidirectional+no_connect"))
    )
    (net (code "40") (name "unconnected-(DD1-PA10-Pad31)") (class "Default")
      (node (ref "DD1") (pin "31") (pinfunction "PA10_31") (pintype "bidirectional+no_connect"))
    )
    (net (code "41") (name "unconnected-(DD1-PB1-Pad19)") (class "Default")
      (node (ref "DD1") (pin "19") (pinfunction "PB1_19") (pintype "bidirectional+no_connect"))
    )
    (net (code "42") (name "unconnected-(DD1-PB3-Pad39)") (class "Default")
      (node (ref "DD1") (pin "39") (pinfunction "PB3_39") (pintype "bidirectional+no_connect"))
    )
    (net (code "43") (name "unconnected-(DD1-PB4-Pad40)") (class "Default")
      (node (ref "DD1") (pin "40") (pinfunction "PB4_40") (pintype "bidirectional+no_connect"))
    )
    (net (code "44") (name "unconnected-(DD1-PB5-Pad41)") (class "Default")
      (node (ref "DD1") (pin "41") (pinfunction "PB5_41") (pintype "bidirectional+no_connect"))
    )
    (net (code "45") (name "unconnected-(DD1-PB6-Pad42)") (class "Default")
      (node (ref "DD1") (pin "42") (pinfunction "PB6_42") (pintype "bidirectional+no_connect"))
    )
    (net (code "46") (name "unconnected-(DD1-PB7-Pad43)") (class "Default")
      (node (ref "DD1") (pin "43") (pinfunction "PB7_43") (pintype "bidirectional+no_connect"))
    )
    (net (code "47") (name "unconnected-(DD1-PB8-Pad45)") (class "Default")
      (node (ref "DD1") (pin "45") (pinfunction "PB8_45") (pintype "bidirectional+no_connect"))
    )
    (net (code "48") (name "unconnected-(DD1-PB9-Pad46)") (class "Default")
      (node (ref "DD1") (pin "46") (pinfunction "PB9_46") (pintype "bidirectional+no_connect"))
    )
    (net (code "49") (name "unconnected-(DD1-PB10-Pad21)") (class "Default")
      (node (ref "DD1") (pin "21") (pinfunction "PB10_21") (pintype "bidirectional+no_connect"))
    )
    (net (code "50") (name "unconnected-(DD1-PB11-Pad22)") (class "Default")
      (node (ref "DD1") (pin "22") (pinfunction "PB11_22") (pintype "bidirectional+no_connect"))
    )
    (net (code "51") (name "unconnected-(DD1-PB15-Pad28)") (class "Default")
      (node (ref "DD1") (pin "28") (pinfunction "PB15_28") (pintype "bidirectional+no_connect"))
    )
    (net (code "52") (name "unconnected-(DD1-PC15-OSC3O-Pad4)") (class "Default")
      (node (ref "DD1") (pin "4") (pinfunction "PC15-OSC3O_4") (pintype "bidirectional+no_connect"))
    )
  )
)
